# RS_485.net
KiCad netlist of a schematic drawn in Altium Designer
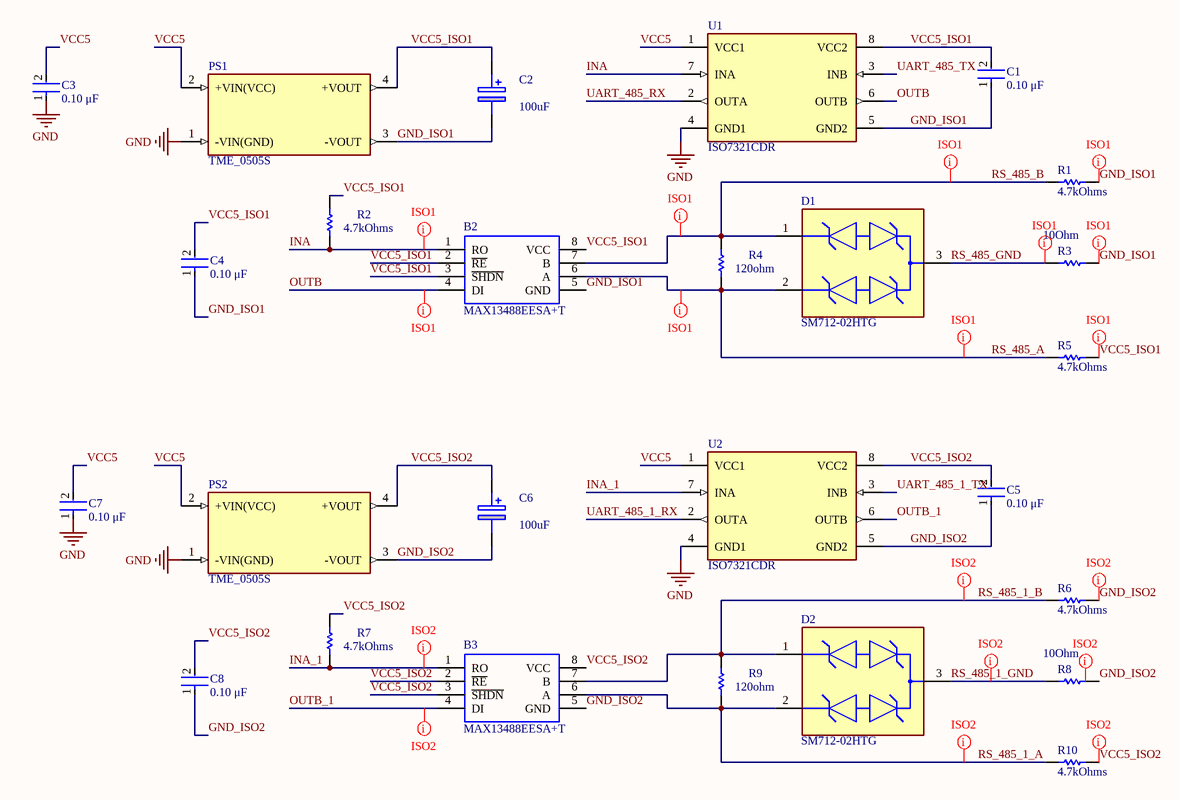
[diagram p0: RS_485.SchDoc]

(export (version "E")
  (design (tool "Eeschema 10.0.6"))
  (components
    (comp (ref "B2")
      (value "MAX13488EESA+T")
      (footprint "SOIC127P600X175-8N")
      (fields (field (name "MOUSER PART NUMBER") "700-MAX13488EESAT"))
      (libsource (lib "Schlib2") (part "MAX13488EESA+T"))
    )
    (comp (ref "B3")
      (value "MAX13488EESA+T")
      (footprint "SOIC127P600X175-8N")
      (fields (field (name "MOUSER PART NUMBER") "700-MAX13488EESAT"))
      (libsource (lib "Schlib2") (part "MAX13488EESA+T"))
    )
    (comp (ref "C1")
      (value "0.10 μF")
      (footprint "FP-C0805C-DN-MFG")
      (description "C0805 0.10 μF X7R 30ppm/°C 10.00% 50 V")
      (fields
        (field (name "MANUFACTURER") "KEMET")
        (field (name "MANUFACTURER PART NUMBER") "C0805C104K5RAC7411")
      )
      (libsource (lib "Altium Content Vault") (part "b4654b650e69147ec39a6b967a45e02"))
    )
    (comp (ref "C2")
      (value "T520B107M006ATE040")
      (footprint "T520B")
      (fields (field (name "MOUSER PART NUMBER") "80-T520B107M6ATE40") (field (name "CAPACITANCE") "100uF"))
      (libsource (lib "Schlib2") (part "T520B107M006ATE040"))
    )
    (comp (ref "C3")
      (value "0.10 μF")
      (footprint "FP-C0805C-DN-MFG")
      (description "C0805 0.10 μF X7R 30ppm/°C 10.00% 50 V")
      (fields
        (field (name "MANUFACTURER") "KEMET")
        (field (name "MANUFACTURER PART NUMBER") "C0805C104K5RAC7411")
      )
      (libsource (lib "Altium Content Vault") (part "b4654b650e69147ec39a6b967a45e02"))
    )
    (comp (ref "C4")
      (value "0.10 μF")
      (footprint "FP-C0805C-DN-MFG")
      (description "C0805 0.10 μF X7R 30ppm/°C 10.00% 50 V")
      (fields
        (field (name "MANUFACTURER") "KEMET")
        (field (name "MANUFACTURER PART NUMBER") "C0805C104K5RAC7411")
      )
      (libsource (lib "Altium Content Vault") (part "b4654b650e69147ec39a6b967a45e02"))
    )
    (comp (ref "C5")
      (value "0.10 μF")
      (footprint "FP-C0805C-DN-MFG")
      (description "C0805 0.10 μF X7R 30ppm/°C 10.00% 50 V")
      (fields
        (field (name "MANUFACTURER") "KEMET")
        (field (name "MANUFACTURER PART NUMBER") "C0805C104K5RAC7411")
      )
      (libsource (lib "Altium Content Vault") (part "b4654b650e69147ec39a6b967a45e02"))
    )
    (comp (ref "C6")
      (value "T520B107M006ATE040")
      (footprint "T520B")
      (fields (field (name "MOUSER PART NUMBER") "80-T520B107M6ATE40") (field (name "CAPACITANCE") "100uF"))
      (libsource (lib "Schlib2") (part "T520B107M006ATE040"))
    )
    (comp (ref "C7")
      (value "0.10 μF")
      (footprint "FP-C0805C-DN-MFG")
      (description "C0805 0.10 μF X7R 30ppm/°C 10.00% 50 V")
      (fields
        (field (name "MANUFACTURER") "KEMET")
        (field (name "MANUFACTURER PART NUMBER") "C0805C104K5RAC7411")
      )
      (libsource (lib "Altium Content Vault") (part "b4654b650e69147ec39a6b967a45e02"))
    )
    (comp (ref "C8")
      (value "0.10 μF")
      (footprint "FP-C0805C-DN-MFG")
      (description "C0805 0.10 μF X7R 30ppm/°C 10.00% 50 V")
      (fields
        (field (name "MANUFACTURER") "KEMET")
        (field (name "MANUFACTURER PART NUMBER") "C0805C104K5RAC7411")
      )
      (libsource (lib "Altium Content Vault") (part "b4654b650e69147ec39a6b967a45e02"))
    )
    (comp (ref "D1")
      (value "SM712-02HTG")
      (footprint "FP-SM712-MFG")
      (description "TVS DIODE 12V 31V SOT23-3")
      (libsource (lib "Altium Content Vault") (part "30adef48d791aa94530531f6d7a3f92"))
    )
    (comp (ref "D2")
      (value "SM712-02HTG")
      (footprint "FP-SM712-MFG")
      (description "TVS DIODE 12V 31V SOT23-3")
      (libsource (lib "Altium Content Vault") (part "30adef48d791aa94530531f6d7a3f92"))
    )
    (comp (ref "PS1")
      (value "TME_0505S")
      (footprint "CONV_TME_0505S")
      (description "1 Watt DC/DC converter, industrial, 10% input, unregulated, encapsulated, SIP-4 package")
      (fields (field (name "MF") "Traco Power") (field (name "MP") "TME 0505S"))
      (libsource (lib "Schlib2") (part "TME_0505S"))
    )
    (comp (ref "PS2")
      (value "TME_0505S")
      (footprint "CONV_TME_0505S")
      (description "1 Watt DC/DC converter, industrial, 10% input, unregulated, encapsulated, SIP-4 package")
      (fields (field (name "MF") "Traco Power") (field (name "MP") "TME 0505S"))
      (libsource (lib "Schlib2") (part "TME_0505S"))
    )
    (comp (ref "R1")
      (value "RC0603FR-074K7L")
      (footprint "RESC1608X55X25LL10T15")
      (description "Chip Resistor, 4.7 KOhm, +/- 1%, 0.1 W, -55 to 155 degC, 0603 (1608 Metric), RoHS, Tape and Reel")
      (fields
        (field (name "MANUFACTURER") "Yageo")
        (field (name "RESISTANCE") "4.7kOhms")
        (field (name "TOLERANCE") "1%")
      )
      (libsource (lib "Altium Content Vault") (part "RES-2"))
    )
    (comp (ref "R2")
      (value "RC0603FR-074K7L")
      (footprint "RESC1608X55X25LL10T15")
      (description "Chip Resistor, 4.7 KOhm, +/- 1%, 0.1 W, -55 to 155 degC, 0603 (1608 Metric), RoHS, Tape and Reel")
      (fields
        (field (name "MANUFACTURER") "Yageo")
        (field (name "RESISTANCE") "4.7kOhms")
        (field (name "TOLERANCE") "1%")
      )
      (libsource (lib "Altium Content Vault") (part "RES-2"))
    )
    (comp (ref "R3")
      (value "RC0805FR-0710RL")
      (footprint "RESC2013X60X35ML10T20")
      (description "Chip Resistor, 10 Ohm, +/- 1%, 0.125 W, -55 to 155 degC, 0805 (2012 Metric), RoHS, Tape and Reel")
      (fields
        (field (name "RESISTANCE") "10Ohm")
        (field (name "MANUFACTURER") "Yageo")
        (field (name "TOLERANCE") "1%")
      )
      (libsource (lib "Altium Content Vault") (part "RES-2"))
    )
    (comp (ref "R4")
      (value "RC1206FR-07120RL")
      (footprint "RESC3116X65X40LL10T20")
      (description "Chip Resistor, 120 Ohm, +/- 1%, 250 mW, -55 to 155 degC, 1206 (3216 Metric), RoHS, Tape and Reel")
      (fields (field (name "RESISTANCE") "120ohm") (field (name "MANUFACTURER") "Yageo"))
      (libsource (lib "Altium Content Vault") (part "RES-2"))
    )
    (comp (ref "R5")
      (value "RC0603FR-074K7L")
      (footprint "RESC1608X55X25LL10T15")
      (description "Chip Resistor, 4.7 KOhm, +/- 1%, 0.1 W, -55 to 155 degC, 0603 (1608 Metric), RoHS, Tape and Reel")
      (fields
        (field (name "MANUFACTURER") "Yageo")
        (field (name "RESISTANCE") "4.7kOhms")
        (field (name "TOLERANCE") "1%")
      )
      (libsource (lib "Altium Content Vault") (part "RES-2"))
    )
    (comp (ref "R6")
      (value "RC0603FR-074K7L")
      (footprint "RESC1608X55X25LL10T15")
      (description "Chip Resistor, 4.7 KOhm, +/- 1%, 0.1 W, -55 to 155 degC, 0603 (1608 Metric), RoHS, Tape and Reel")
      (fields
        (field (name "MANUFACTURER") "Yageo")
        (field (name "RESISTANCE") "4.7kOhms")
        (field (name "TOLERANCE") "1%")
      )
      (libsource (lib "Altium Content Vault") (part "RES-2"))
    )
    (comp (ref "R7")
      (value "RC0603FR-074K7L")
      (footprint "RESC1608X55X25LL10T15")
      (description "Chip Resistor, 4.7 KOhm, +/- 1%, 0.1 W, -55 to 155 degC, 0603 (1608 Metric), RoHS, Tape and Reel")
      (fields
        (field (name "MANUFACTURER") "Yageo")
        (field (name "RESISTANCE") "4.7kOhms")
        (field (name "TOLERANCE") "1%")
      )
      (libsource (lib "Altium Content Vault") (part "RES-2"))
    )
    (comp (ref "R8")
      (value "RC0805FR-0710RL")
      (footprint "RESC2013X60X35ML10T20")
      (description "Chip Resistor, 10 Ohm, +/- 1%, 0.125 W, -55 to 155 degC, 0805 (2012 Metric), RoHS, Tape and Reel")
      (fields
        (field (name "RESISTANCE") "10Ohm")
        (field (name "MANUFACTURER") "Yageo")
        (field (name "TOLERANCE") "1%")
      )
      (libsource (lib "Altium Content Vault") (part "RES-2"))
    )
    (comp (ref "R9")
      (value "RC1206FR-07120RL")
      (footprint "RESC3116X65X40LL10T20")
      (description "Chip Resistor, 120 Ohm, +/- 1%, 250 mW, -55 to 155 degC, 1206 (3216 Metric), RoHS, Tape and Reel")
      (fields (field (name "RESISTANCE") "120ohm") (field (name "MANUFACTURER") "Yageo"))
      (libsource (lib "Altium Content Vault") (part "RES-2"))
    )
    (comp (ref "R10")
      (value "RC0603FR-074K7L")
      (footprint "RESC1608X55X25LL10T15")
      (description "Chip Resistor, 4.7 KOhm, +/- 1%, 0.1 W, -55 to 155 degC, 0603 (1608 Metric), RoHS, Tape and Reel")
      (fields
        (field (name "MANUFACTURER") "Yageo")
        (field (name "RESISTANCE") "4.7kOhms")
        (field (name "TOLERANCE") "1%")
      )
      (libsource (lib "Altium Content Vault") (part "RES-2"))
    )
    (comp (ref "U1")
      (value "ISO7321CDR")
      (footprint "FP-D0008B-MFG")
      (description "DGTL ISO 3000VRMS 2CH GP 8SOIC")
      (libsource (lib "Altium Content Vault") (part "d92c9f897ec604fcf64456104b7740e"))
    )
    (comp (ref "U2")
      (value "ISO7321CDR")
      (footprint "FP-D0008B-MFG")
      (description "DGTL ISO 3000VRMS 2CH GP 8SOIC")
      (libsource (lib "Altium Content Vault") (part "d92c9f897ec604fcf64456104b7740e"))
    )
  )
  (nets
    (net (code "1") (name "/GND_ISO1") (class "Default")
      (node (ref "B2") (pin "5") (pinfunction "GND_5") (pintype "passive"))
      (node (ref "C1") (pin "1") (pinfunction "1_1") (pintype "passive"))
      (node (ref "C2") (pin "2") (pinfunction "-_2") (pintype "passive"))
      (node (ref "C4") (pin "1") (pinfunction "1_1") (pintype "passive"))
      (node (ref "PS1") (pin "3") (pinfunction "-VOUT_3") (pintype "output"))
      (node (ref "R1") (pin "1") (pinfunction "1_1") (pintype "passive"))
      (node (ref "R3") (pin "2") (pinfunction "2_2") (pintype "passive"))
      (node (ref "U1") (pin "5") (pinfunction "GND2_5") (pintype "power_in"))
    )
    (net (code "2") (name "/GND_ISO2") (class "Default")
      (node (ref "B3") (pin "5") (pinfunction "GND_5") (pintype "passive"))
      (node (ref "C5") (pin "1") (pinfunction "1_1") (pintype "passive"))
      (node (ref "C6") (pin "2") (pinfunction "-_2") (pintype "passive"))
      (node (ref "C8") (pin "1") (pinfunction "1_1") (pintype "passive"))
      (node (ref "PS2") (pin "3") (pinfunction "-VOUT_3") (pintype "output"))
      (node (ref "R6") (pin "1") (pinfunction "1_1") (pintype "passive"))
      (node (ref "R8") (pin "2") (pinfunction "2_2") (pintype "passive"))
      (node (ref "U2") (pin "5") (pinfunction "GND2_5") (pintype "power_in"))
    )
    (net (code "3") (name "/INA") (class "Default")
      (node (ref "B2") (pin "1") (pinfunction "RO_1") (pintype "passive"))
      (node (ref "R2") (pin "1") (pinfunction "1_1") (pintype "passive"))
      (node (ref "U1") (pin "7") (pinfunction "INA_7") (pintype "input"))
    )
    (net (code "4") (name "/INA_1") (class "Default")
      (node (ref "B3") (pin "1") (pinfunction "RO_1") (pintype "passive"))
      (node (ref "R7") (pin "1") (pinfunction "1_1") (pintype "passive"))
      (node (ref "U2") (pin "7") (pinfunction "INA_7") (pintype "input"))
    )
    (net (code "5") (name "/OUTB") (class "Default")
      (node (ref "B2") (pin "4") (pinfunction "DI_4") (pintype "passive"))
      (node (ref "U1") (pin "6") (pinfunction "OUTB_6") (pintype "output"))
    )
    (net (code "6") (name "/OUTB_1") (class "Default")
      (node (ref "B3") (pin "4") (pinfunction "DI_4") (pintype "passive"))
      (node (ref "U2") (pin "6") (pinfunction "OUTB_6") (pintype "output"))
    )
    (net (code "7") (name "/RS_485_1_A") (class "Default")
      (node (ref "B3") (pin "6") (pinfunction "A_6") (pintype "passive"))
      (node (ref "D2") (pin "2") (pinfunction "2_2") (pintype "passive"))
      (node (ref "R10") (pin "2") (pinfunction "2_2") (pintype "passive"))
      (node (ref "R9") (pin "1") (pinfunction "1_1") (pintype "passive"))
    )
    (net (code "8") (name "/RS_485_1_B") (class "Default")
      (node (ref "B3") (pin "7") (pinfunction "B_7") (pintype "passive"))
      (node (ref "D2") (pin "1") (pinfunction "1_1") (pintype "passive"))
      (node (ref "R6") (pin "2") (pinfunction "2_2") (pintype "passive"))
      (node (ref "R9") (pin "2") (pinfunction "2_2") (pintype "passive"))
    )
    (net (code "9") (name "/RS_485_1_GND") (class "Default")
      (node (ref "D2") (pin "3") (pinfunction "3_3") (pintype "passive"))
      (node (ref "R8") (pin "1") (pinfunction "1_1") (pintype "passive"))
    )
    (net (code "10") (name "/RS_485_A") (class "Default")
      (node (ref "B2") (pin "6") (pinfunction "A_6") (pintype "passive"))
      (node (ref "D1") (pin "2") (pinfunction "2_2") (pintype "passive"))
      (node (ref "R4") (pin "1") (pinfunction "1_1") (pintype "passive"))
      (node (ref "R5") (pin "2") (pinfunction "2_2") (pintype "passive"))
    )
    (net (code "11") (name "/RS_485_B") (class "Default")
      (node (ref "B2") (pin "7") (pinfunction "B_7") (pintype "passive"))
      (node (ref "D1") (pin "1") (pinfunction "1_1") (pintype "passive"))
      (node (ref "R1") (pin "2") (pinfunction "2_2") (pintype "passive"))
      (node (ref "R4") (pin "2") (pinfunction "2_2") (pintype "passive"))
    )
    (net (code "12") (name "/RS_485_GND") (class "Default")
      (node (ref "D1") (pin "3") (pinfunction "3_3") (pintype "passive"))
      (node (ref "R3") (pin "1") (pinfunction "1_1") (pintype "passive"))
    )
    (net (code "13") (name "/UART_485_1_RX") (class "Default")
      (node (ref "U2") (pin "2") (pinfunction "OUTA_2") (pintype "output"))
    )
    (net (code "14") (name "/UART_485_1_TX") (class "Default")
      (node (ref "U2") (pin "3") (pinfunction "INB_3") (pintype "input"))
    )
    (net (code "15") (name "/UART_485_RX") (class "Default")
      (node (ref "U1") (pin "2") (pinfunction "OUTA_2") (pintype "output"))
    )
    (net (code "16") (name "/UART_485_TX") (class "Default")
      (node (ref "U1") (pin "3") (pinfunction "INB_3") (pintype "input"))
    )
    (net (code "17") (name "/VCC5") (class "Default")
      (node (ref "C3") (pin "2") (pinfunction "2_2") (pintype "passive"))
      (node (ref "C7") (pin "2") (pinfunction "2_2") (pintype "passive"))
      (node (ref "PS1") (pin "2") (pinfunction "+VIN(VCC)_2") (pintype "input"))
      (node (ref "PS2") (pin "2") (pinfunction "+VIN(VCC)_2") (pintype "input"))
      (node (ref "U1") (pin "1") (pinfunction "VCC1_1") (pintype "power_in"))
      (node (ref "U2") (pin "1") (pinfunction "VCC1_1") (pintype "power_in"))
    )
    (net (code "18") (name "/VCC5_ISO1") (class "Default")
      (node (ref "B2") (pin "2") (pinfunction "RE_2") (pintype "passive"))
      (node (ref "B2") (pin "3") (pinfunction "SHDN_3") (pintype "passive"))
      (node (ref "B2") (pin "8") (pinfunction "VCC_8") (pintype "passive"))
      (node (ref "C1") (pin "2") (pinfunction "2_2") (pintype "passive"))
      (node (ref "C2") (pin "1") (pinfunction "+_1") (pintype "passive"))
      (node (ref "C4") (pin "2") (pinfunction "2_2") (pintype "passive"))
      (node (ref "PS1") (pin "4") (pinfunction "+VOUT_4") (pintype "output"))
      (node (ref "R2") (pin "2") (pinfunction "2_2") (pintype "passive"))
      (node (ref "R5") (pin "1") (pinfunction "1_1") (pintype "passive"))
      (node (ref "U1") (pin "8") (pinfunction "VCC2_8") (pintype "power_in"))
    )
    (net (code "19") (name "/VCC5_ISO2") (class "Default")
      (node (ref "B3") (pin "2") (pinfunction "RE_2") (pintype "passive"))
      (node (ref "B3") (pin "3") (pinfunction "SHDN_3") (pintype "passive"))
      (node (ref "B3") (pin "8") (pinfunction "VCC_8") (pintype "passive"))
      (node (ref "C5") (pin "2") (pinfunction "2_2") (pintype "passive"))
      (node (ref "C6") (pin "1") (pinfunction "+_1") (pintype "passive"))
      (node (ref "C8") (pin "2") (pinfunction "2_2") (pintype "passive"))
      (node (ref "PS2") (pin "4") (pinfunction "+VOUT_4") (pintype "output"))
      (node (ref "R10") (pin "1") (pinfunction "1_1") (pintype "passive"))
      (node (ref "R7") (pin "2") (pinfunction "2_2") (pintype "passive"))
      (node (ref "U2") (pin "8") (pinfunction "VCC2_8") (pintype "power_in"))
    )
    (net (code "20") (name "GND") (class "Default")
      (node (ref "C3") (pin "1") (pinfunction "1_1") (pintype "passive"))
      (node (ref "C7") (pin "1") (pinfunction "1_1") (pintype "passive"))
      (node (ref "PS1") (pin "1") (pinfunction "-VIN(GND)_1") (pintype "input"))
      (node (ref "PS2") (pin "1") (pinfunction "-VIN(GND)_1") (pintype "input"))
      (node (ref "U1") (pin "4") (pinfunction "GND1_4") (pintype "power_in"))
      (node (ref "U2") (pin "4") (pinfunction "GND1_4") (pintype "power_in"))
    )
  )
)
